# task1_digital.net
KiCad netlist of a schematic drawn in EAGLE
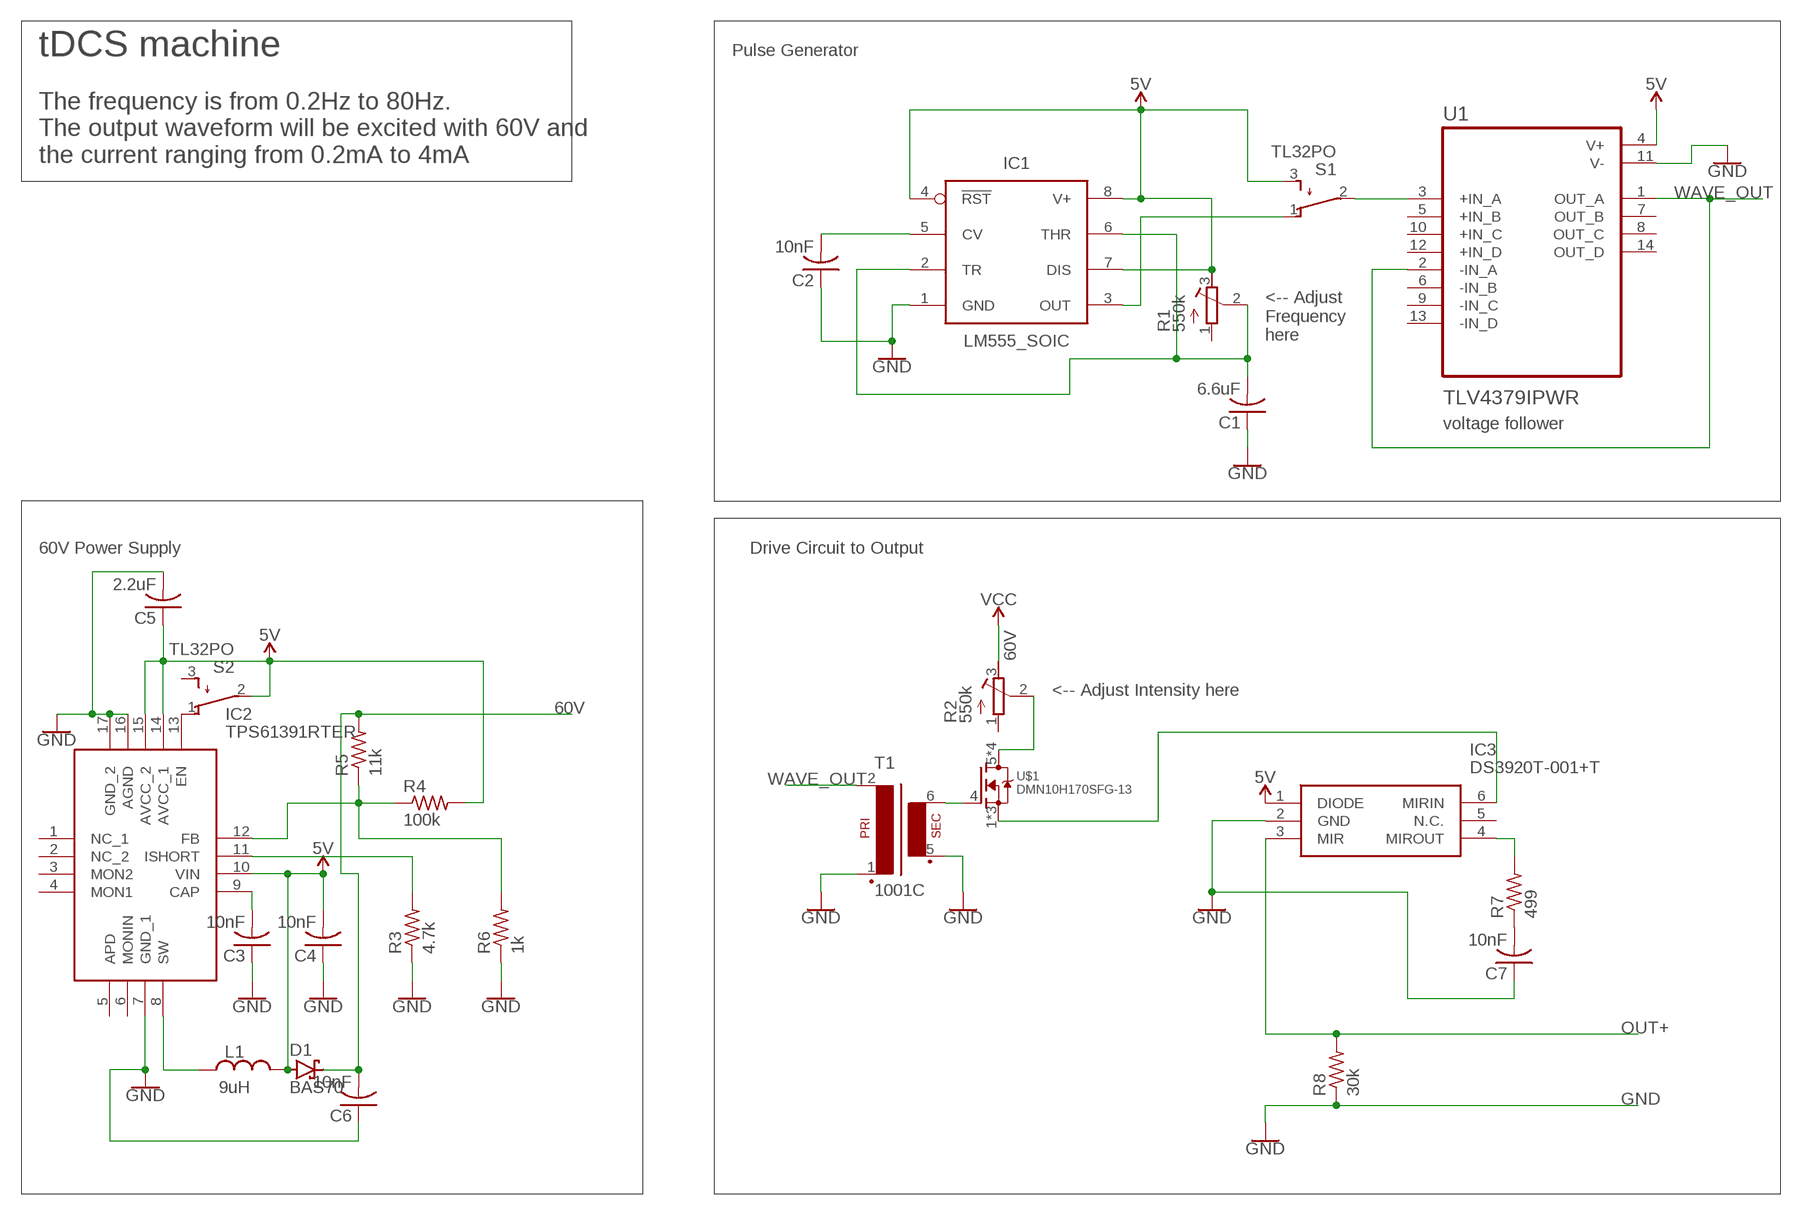
[diagram p0: schematic, sheet 1]

(export (version "E")
  (design (tool "Eeschema 10.0.6"))
  (components
    (comp (ref "C1")
      (value "6.6uF")
      (footprint "eagle-import:C0805")
      (libsource (lib "eagle-import") (part "C-USC0805"))
    )
    (comp (ref "C2")
      (value "10nF")
      (footprint "eagle-import:C0805")
      (libsource (lib "eagle-import") (part "C-USC0805"))
    )
    (comp (ref "C3")
      (value "10nF")
      (footprint "eagle-import:C0805")
      (libsource (lib "eagle-import") (part "C-USC0805"))
    )
    (comp (ref "C4")
      (value "10nF")
      (footprint "eagle-import:C0805")
      (libsource (lib "eagle-import") (part "C-USC0805"))
    )
    (comp (ref "C5")
      (value "2.2uF")
      (footprint "eagle-import:C0805")
      (libsource (lib "eagle-import") (part "C-USC0805"))
    )
    (comp (ref "C6")
      (value "10nF")
      (footprint "eagle-import:C0805")
      (libsource (lib "eagle-import") (part "C-USC0805"))
    )
    (comp (ref "C7")
      (value "10nF")
      (footprint "eagle-import:C0805")
      (libsource (lib "eagle-import") (part "C-USC0805"))
    )
    (comp (ref "D1")
      (value "BAS70")
      (footprint "eagle-import:SOT23")
      (libsource (lib "eagle-import") (part "BAS70"))
    )
    (comp (ref "IC1")
      (value "LM555_SOIC")
      (footprint "eagle-import:SOIC127P599X175-8N")
      (fields (field (name "MANUFACTURER") "Texas Instruments ") (field (name "MPN") "LM555CM/NOPB "))
      (libsource (lib "eagle-import") (part "555_SOICLM"))
    )
    (comp (ref "IC2")
      (value "TPS61391RTER")
      (footprint "eagle-import:QFN50P300X300X80-17N")
      (fields (field (name "MOUSER_PART_NUMBER") "595-TPS61391RTER"))
      (libsource (lib "eagle-import") (part "TPS61391RTER"))
    )
    (comp (ref "IC3")
      (value "DS3920T-001+T")
      (footprint "eagle-import:SOT95P280X145-6N")
      (fields (field (name "MOUSER_PART_NUMBER") "700-DS3920T-001+T"))
      (libsource (lib "eagle-import") (part "DS3920T-001+T"))
    )
    (comp (ref "L1")
      (value "9uH")
      (footprint "eagle-import:INDC3216X190")
      (libsource (lib "eagle-import") (part "LCHIP-1206(3216-METRIC)_"))
    )
    (comp (ref "R1")
      (value "550k")
      (footprint "eagle-import:RTRIM4G_J")
      (libsource (lib "eagle-import") (part "R-TRIMM4G/J"))
    )
    (comp (ref "R2")
      (value "550k")
      (footprint "eagle-import:RTRIM4G_J")
      (libsource (lib "eagle-import") (part "R-TRIMM4G/J"))
    )
    (comp (ref "R3")
      (value "4.7k")
      (footprint "eagle-import:R0805")
      (libsource (lib "eagle-import") (part "R-US_R0805"))
    )
    (comp (ref "R4")
      (value "100k")
      (footprint "eagle-import:R0805")
      (libsource (lib "eagle-import") (part "R-US_R0805"))
    )
    (comp (ref "R5")
      (value "11k")
      (footprint "eagle-import:R0805")
      (libsource (lib "eagle-import") (part "R-US_R0805"))
    )
    (comp (ref "R6")
      (value "1k")
      (footprint "eagle-import:R0805")
      (libsource (lib "eagle-import") (part "R-US_R0805"))
    )
    (comp (ref "R7")
      (value "499")
      (footprint "eagle-import:R0805")
      (libsource (lib "eagle-import") (part "R-US_R0805"))
    )
    (comp (ref "R8")
      (value "30k")
      (footprint "eagle-import:R0805")
      (libsource (lib "eagle-import") (part "R-US_R0805"))
    )
    (comp (ref "S1")
      (value "TL32PO")
      (footprint "eagle-import:TL3XPO")
      (libsource (lib "eagle-import") (part "TL32PO"))
    )
    (comp (ref "S2")
      (value "TL32PO")
      (footprint "eagle-import:TL3XPO")
      (libsource (lib "eagle-import") (part "TL32PO"))
    )
    (comp (ref "T1")
      (value "1001C")
      (footprint "eagle-import:1001")
      (fields (field (name "MF") "Murata Power"))
      (libsource (lib "eagle-import") (part "1001C"))
    )
    (comp (ref "U$1")
      (value "DMN10H170SFG-13")
      (footprint "eagle-import:TRANS_DMP3017SFGQ-7")
      (libsource (lib "eagle-import") (part "DMN10H170SFG-13"))
    )
    (comp (ref "U1")
      (value "TLV4379IPWR")
      (footprint "eagle-import:SOP65P640X120-14N")
      (fields (field (name "MF") "Texas Instruments"))
      (libsource (lib "eagle-import") (part "TLV4379IPWR"))
    )
  )
  (nets
    (net (code "1") (name "/OUT+") (class "Default")
      (node (ref "IC3") (pin "3") (pinfunction "MIR_3") (pintype "bidirectional"))
      (node (ref "R8") (pin "2") (pinfunction "2_2") (pintype "passive"))
    )
    (net (code "2") (name "/WAVE_OUT") (class "Default")
      (node (ref "T1") (pin "2") (pinfunction "P2_2") (pintype "passive"))
      (node (ref "U1") (pin "1") (pinfunction "OUT_A_1") (pintype "output"))
      (node (ref "U1") (pin "2") (pinfunction "-IN_A_2") (pintype "input"))
    )
    (net (code "3") (name "5V") (class "Default")
      (node (ref "C4") (pin "2") (pinfunction "2_2") (pintype "passive"))
      (node (ref "C5") (pin "1") (pinfunction "1_1") (pintype "passive"))
      (node (ref "D1") (pin "1") (pinfunction "A_1") (pintype "passive"))
      (node (ref "IC1") (pin "4") (pinfunction "~{RST}_4") (pintype "input"))
      (node (ref "IC1") (pin "7") (pinfunction "DIS_7") (pintype "input"))
      (node (ref "IC1") (pin "8") (pinfunction "V+_8") (pintype "power_in"))
      (node (ref "IC2") (pin "10") (pinfunction "VIN_10") (pintype "bidirectional"))
      (node (ref "IC2") (pin "14") (pinfunction "AVCC_1_14") (pintype "bidirectional"))
      (node (ref "IC2") (pin "15") (pinfunction "AVCC_2_15") (pintype "bidirectional"))
      (node (ref "IC3") (pin "1") (pinfunction "DIODE_1") (pintype "bidirectional"))
      (node (ref "L1") (pin "2") (pinfunction "2_2") (pintype "passive"))
      (node (ref "R1") (pin "3") (pinfunction "E_3") (pintype "passive"))
      (node (ref "R4") (pin "2") (pinfunction "2_2") (pintype "passive"))
      (node (ref "S1") (pin "3") (pinfunction "S_3") (pintype "passive"))
      (node (ref "S2") (pin "2") (pinfunction "P_2") (pintype "passive"))
      (node (ref "U1") (pin "4") (pinfunction "V+_4") (pintype "power_in"))
    )
    (net (code "4") (name "GND") (class "Default")
      (node (ref "C1") (pin "1") (pinfunction "1_1") (pintype "passive"))
      (node (ref "C2") (pin "1") (pinfunction "1_1") (pintype "passive"))
      (node (ref "C3") (pin "1") (pinfunction "1_1") (pintype "passive"))
      (node (ref "C4") (pin "1") (pinfunction "1_1") (pintype "passive"))
      (node (ref "C5") (pin "2") (pinfunction "2_2") (pintype "passive"))
      (node (ref "C6") (pin "1") (pinfunction "1_1") (pintype "passive"))
      (node (ref "C7") (pin "1") (pinfunction "1_1") (pintype "passive"))
      (node (ref "IC1") (pin "1") (pinfunction "GND_1") (pintype "power_in"))
      (node (ref "IC2") (pin "16") (pinfunction "AGND_16") (pintype "bidirectional"))
      (node (ref "IC2") (pin "17") (pinfunction "GND_2_17") (pintype "bidirectional"))
      (node (ref "IC2") (pin "7") (pinfunction "GND_1_7") (pintype "bidirectional"))
      (node (ref "IC3") (pin "2") (pinfunction "GND_2") (pintype "bidirectional"))
      (node (ref "R3") (pin "1") (pinfunction "1_1") (pintype "passive"))
      (node (ref "R6") (pin "1") (pinfunction "1_1") (pintype "passive"))
      (node (ref "R8") (pin "1") (pinfunction "1_1") (pintype "passive"))
      (node (ref "T1") (pin "1") (pinfunction "P1_1") (pintype "passive"))
      (node (ref "T1") (pin "5") (pinfunction "S1_5") (pintype "passive"))
      (node (ref "U1") (pin "11") (pinfunction "V-_11") (pintype "power_in"))
    )
    (net (code "5") (name "Net-(C7-Pad2)") (class "Default")
      (node (ref "C7") (pin "2") (pinfunction "2_2") (pintype "passive"))
      (node (ref "R7") (pin "1") (pinfunction "1_1") (pintype "passive"))
    )
    (net (code "6") (name "Net-(IC1-CV)") (class "Default")
      (node (ref "C2") (pin "2") (pinfunction "2_2") (pintype "passive"))
      (node (ref "IC1") (pin "5") (pinfunction "CV_5") (pintype "input"))
    )
    (net (code "7") (name "Net-(IC1-OUT)") (class "Default")
      (node (ref "IC1") (pin "3") (pinfunction "OUT_3") (pintype "output"))
      (node (ref "S1") (pin "1") (pinfunction "O_1") (pintype "passive"))
    )
    (net (code "8") (name "Net-(IC1-THR)") (class "Default")
      (node (ref "C1") (pin "2") (pinfunction "2_2") (pintype "passive"))
      (node (ref "IC1") (pin "2") (pinfunction "TR_2") (pintype "input"))
      (node (ref "IC1") (pin "6") (pinfunction "THR_6") (pintype "input"))
      (node (ref "R1") (pin "2") (pinfunction "S_2") (pintype "passive"))
    )
    (net (code "9") (name "Net-(IC2-CAP)") (class "Default")
      (node (ref "C3") (pin "2") (pinfunction "2_2") (pintype "passive"))
      (node (ref "IC2") (pin "9") (pinfunction "CAP_9") (pintype "bidirectional"))
    )
    (net (code "10") (name "Net-(IC2-EN)") (class "Default")
      (node (ref "IC2") (pin "13") (pinfunction "EN_13") (pintype "bidirectional"))
      (node (ref "S2") (pin "1") (pinfunction "O_1") (pintype "passive"))
    )
    (net (code "11") (name "Net-(IC2-FB)") (class "Default")
      (node (ref "IC2") (pin "12") (pinfunction "FB_12") (pintype "bidirectional"))
      (node (ref "R4") (pin "1") (pinfunction "1_1") (pintype "passive"))
      (node (ref "R5") (pin "1") (pinfunction "1_1") (pintype "passive"))
      (node (ref "R6") (pin "2") (pinfunction "2_2") (pintype "passive"))
    )
    (net (code "12") (name "Net-(IC2-ISHORT)") (class "Default")
      (node (ref "IC2") (pin "11") (pinfunction "ISHORT_11") (pintype "bidirectional"))
      (node (ref "R3") (pin "2") (pinfunction "2_2") (pintype "passive"))
    )
    (net (code "13") (name "Net-(IC2-SW)") (class "Default")
      (node (ref "IC2") (pin "8") (pinfunction "SW_8") (pintype "bidirectional"))
      (node (ref "L1") (pin "1") (pinfunction "1_1") (pintype "passive"))
    )
    (net (code "14") (name "Net-(IC3-MIRIN)") (class "Default")
      (node (ref "IC3") (pin "6") (pinfunction "MIRIN_6") (pintype "bidirectional"))
      (node (ref "U$1") (pin "1") (pinfunction "S_1") (pintype "bidirectional"))
      (node (ref "U$1") (pin "2") (pinfunction "S_2") (pintype "bidirectional"))
      (node (ref "U$1") (pin "3") (pinfunction "S_3") (pintype "bidirectional"))
    )
    (net (code "15") (name "Net-(IC3-MIROUT)") (class "Default")
      (node (ref "IC3") (pin "4") (pinfunction "MIROUT_4") (pintype "bidirectional"))
      (node (ref "R7") (pin "2") (pinfunction "2_2") (pintype "passive"))
    )
    (net (code "16") (name "Net-(R2-S)") (class "Default")
      (node (ref "R2") (pin "2") (pinfunction "S_2") (pintype "passive"))
      (node (ref "U$1") (pin "5") (pinfunction "D_5") (pintype "bidirectional"))
      (node (ref "U$1") (pin "6") (pinfunction "D_6") (pintype "bidirectional"))
      (node (ref "U$1") (pin "7") (pinfunction "D_7") (pintype "bidirectional"))
      (node (ref "U$1") (pin "8") (pinfunction "D_8") (pintype "bidirectional"))
    )
    (net (code "17") (name "Net-(S1-P)") (class "Default")
      (node (ref "S1") (pin "2") (pinfunction "P_2") (pintype "passive"))
      (node (ref "U1") (pin "3") (pinfunction "+IN_A_3") (pintype "input"))
    )
    (net (code "18") (name "Net-(T1-S2)") (class "Default")
      (node (ref "T1") (pin "6") (pinfunction "S2_6") (pintype "passive"))
      (node (ref "U$1") (pin "4") (pinfunction "G_4") (pintype "bidirectional"))
    )
    (net (code "19") (name "VCC") (class "Default")
      (node (ref "C6") (pin "2") (pinfunction "2_2") (pintype "passive"))
      (node (ref "D1") (pin "3") (pinfunction "C_3") (pintype "passive"))
      (node (ref "R2") (pin "3") (pinfunction "E_3") (pintype "passive"))
      (node (ref "R5") (pin "2") (pinfunction "2_2") (pintype "passive"))
    )
    (net (code "20") (name "unconnected-(IC2-APD-Pad5)") (class "Default")
      (node (ref "IC2") (pin "5") (pinfunction "APD_5") (pintype "bidirectional"))
    )
    (net (code "21") (name "unconnected-(IC2-MON1-Pad4)") (class "Default")
      (node (ref "IC2") (pin "4") (pinfunction "MON1_4") (pintype "bidirectional"))
    )
    (net (code "22") (name "unconnected-(IC2-MON2-Pad3)") (class "Default")
      (node (ref "IC2") (pin "3") (pinfunction "MON2_3") (pintype "bidirectional"))
    )
    (net (code "23") (name "unconnected-(IC2-MONIN-Pad6)") (class "Default")
      (node (ref "IC2") (pin "6") (pinfunction "MONIN_6") (pintype "bidirectional"))
    )
    (net (code "24") (name "unconnected-(IC2-NC_1-Pad1)") (class "Default")
      (node (ref "IC2") (pin "1") (pinfunction "NC_1_1") (pintype "bidirectional"))
    )
    (net (code "25") (name "unconnected-(IC2-NC_2-Pad2)") (class "Default")
      (node (ref "IC2") (pin "2") (pinfunction "NC_2_2") (pintype "bidirectional"))
    )
    (net (code "26") (name "unconnected-(IC3-N.C.-Pad5)") (class "Default")
      (node (ref "IC3") (pin "5") (pinfunction "N.C._5") (pintype "no_connect"))
    )
    (net (code "27") (name "unconnected-(R1-A-Pad1)") (class "Default")
      (node (ref "R1") (pin "1") (pinfunction "A_1") (pintype "passive"))
    )
    (net (code "28") (name "unconnected-(R2-A-Pad1)") (class "Default")
      (node (ref "R2") (pin "1") (pinfunction "A_1") (pintype "passive"))
    )
    (net (code "29") (name "unconnected-(S2-S-Pad3)") (class "Default")
      (node (ref "S2") (pin "3") (pinfunction "S_3") (pintype "passive"))
    )
    (net (code "30") (name "unconnected-(U1-+IN_B-Pad5)") (class "Default")
      (node (ref "U1") (pin "5") (pinfunction "+IN_B_5") (pintype "input"))
    )
    (net (code "31") (name "unconnected-(U1-+IN_C-Pad10)") (class "Default")
      (node (ref "U1") (pin "10") (pinfunction "+IN_C_10") (pintype "input"))
    )
    (net (code "32") (name "unconnected-(U1-+IN_D-Pad12)") (class "Default")
      (node (ref "U1") (pin "12") (pinfunction "+IN_D_12") (pintype "input"))
    )
    (net (code "33") (name "unconnected-(U1--IN_B-Pad6)") (class "Default")
      (node (ref "U1") (pin "6") (pinfunction "-IN_B_6") (pintype "input"))
    )
    (net (code "34") (name "unconnected-(U1--IN_C-Pad9)") (class "Default")
      (node (ref "U1") (pin "9") (pinfunction "-IN_C_9") (pintype "input"))
    )
    (net (code "35") (name "unconnected-(U1--IN_D-Pad13)") (class "Default")
      (node (ref "U1") (pin "13") (pinfunction "-IN_D_13") (pintype "input"))
    )
    (net (code "36") (name "unconnected-(U1-OUT_B-Pad7)") (class "Default")
      (node (ref "U1") (pin "7") (pinfunction "OUT_B_7") (pintype "output"))
    )
    (net (code "37") (name "unconnected-(U1-OUT_C-Pad8)") (class "Default")
      (node (ref "U1") (pin "8") (pinfunction "OUT_C_8") (pintype "output"))
    )
    (net (code "38") (name "unconnected-(U1-OUT_D-Pad14)") (class "Default")
      (node (ref "U1") (pin "14") (pinfunction "OUT_D_14") (pintype "output"))
    )
  )
)
